# LIS3MDL.net
KiCad netlist of a schematic drawn in Altium Designer
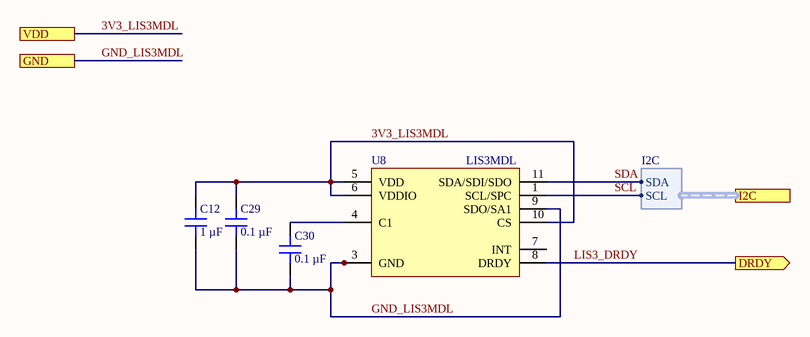
[diagram p0: LIS3MDL.SchDoc]

(export (version "E")
  (design (tool "Eeschema 10.0.6"))
  (components
    (comp (ref "C12")
      (value "1 µF")
      (footprint "CAP 0402_1005")
      (description "CAP CER 0.1UF 16V X7R 0402")
      (fields (field (name "PART NUMBER") "C0402C104K4RACAUTO") (field (name "MANUFACTURER") "KEMET"))
      (libsource (lib "Celestial Altium Library - altium_library") (part "Capacitor"))
    )
    (comp (ref "C29")
      (value "0.1 µF")
      (footprint "CAP 0402_1005")
      (description "CAP CER 0.1UF 16V X7R 0402")
      (fields (field (name "PART NUMBER") "C0402C104K4RACAUTO") (field (name "MANUFACTURER") "KEMET"))
      (libsource (lib "Celestial Altium Library - altium_library") (part "Capacitor"))
    )
    (comp (ref "C30")
      (value "0.1 µF")
      (footprint "CAP 0402_1005")
      (description "CAP CER 0.1UF 16V X7R 0402")
      (fields (field (name "PART NUMBER") "C0402C104K4RACAUTO") (field (name "MANUFACTURER") "KEMET"))
      (libsource (lib "Celestial Altium Library - altium_library") (part "Capacitor"))
    )
    (comp (ref "U8")
      (value "LIS3MDL")
      (footprint "LGA12_ST")
      (description "Magnetometer")
      (libsource (lib "IC") (part "LIS3MDL"))
    )
  )
  (nets
    (net (code "2") (name "/3V3_LIS3MDL") (class "Default")
      (node (ref "C12") (pin "1") (pinfunction "1_1") (pintype "passive"))
      (node (ref "C29") (pin "1") (pinfunction "1_1") (pintype "passive"))
      (node (ref "U8") (pin "10") (pinfunction "CS_10") (pintype "passive"))
      (node (ref "U8") (pin "5") (pinfunction "VDD_5") (pintype "passive"))
      (node (ref "U8") (pin "6") (pinfunction "VDDIO_6") (pintype "passive"))
    )
    (net (code "3") (name "/GND_LIS3MDL") (class "Default")
      (node (ref "C12") (pin "2") (pinfunction "2_2") (pintype "passive"))
      (node (ref "C29") (pin "2") (pinfunction "2_2") (pintype "passive"))
      (node (ref "C30") (pin "2") (pinfunction "2_2") (pintype "passive"))
      (node (ref "U8") (pin "12") (pinfunction "Reserved_12") (pintype "passive"))
      (node (ref "U8") (pin "2") (pinfunction "Reserved_2") (pintype "passive"))
      (node (ref "U8") (pin "3") (pinfunction "GND_3") (pintype "passive"))
      (node (ref "U8") (pin "9") (pinfunction "SDO/SA1_9") (pintype "passive"))
    )
    (net (code "4") (name "/LIS3_DRDY") (class "Default")
      (node (ref "U8") (pin "8") (pinfunction "DRDY_8") (pintype "passive"))
    )
    (net (code "5") (name "/SCL") (class "Default")
      (node (ref "U8") (pin "1") (pinfunction "SCL/SPC_1") (pintype "passive"))
    )
    (net (code "6") (name "/SDA") (class "Default")
      (node (ref "U8") (pin "11") (pinfunction "SDA/SDI/SDO_11") (pintype "passive"))
    )
    (net (code "8") (name "Net-(U8-C1)") (class "Default")
      (node (ref "C30") (pin "1") (pinfunction "1_1") (pintype "passive"))
      (node (ref "U8") (pin "4") (pinfunction "C1_4") (pintype "passive"))
    )
    (net (code "9") (name "unconnected-(U8-INT-Pad7)") (class "Default")
      (node (ref "U8") (pin "7") (pinfunction "INT_7") (pintype "passive"))
    )
  )
)
